# variator_380V.net
KiCad netlist of a schematic drawn in EAGLE
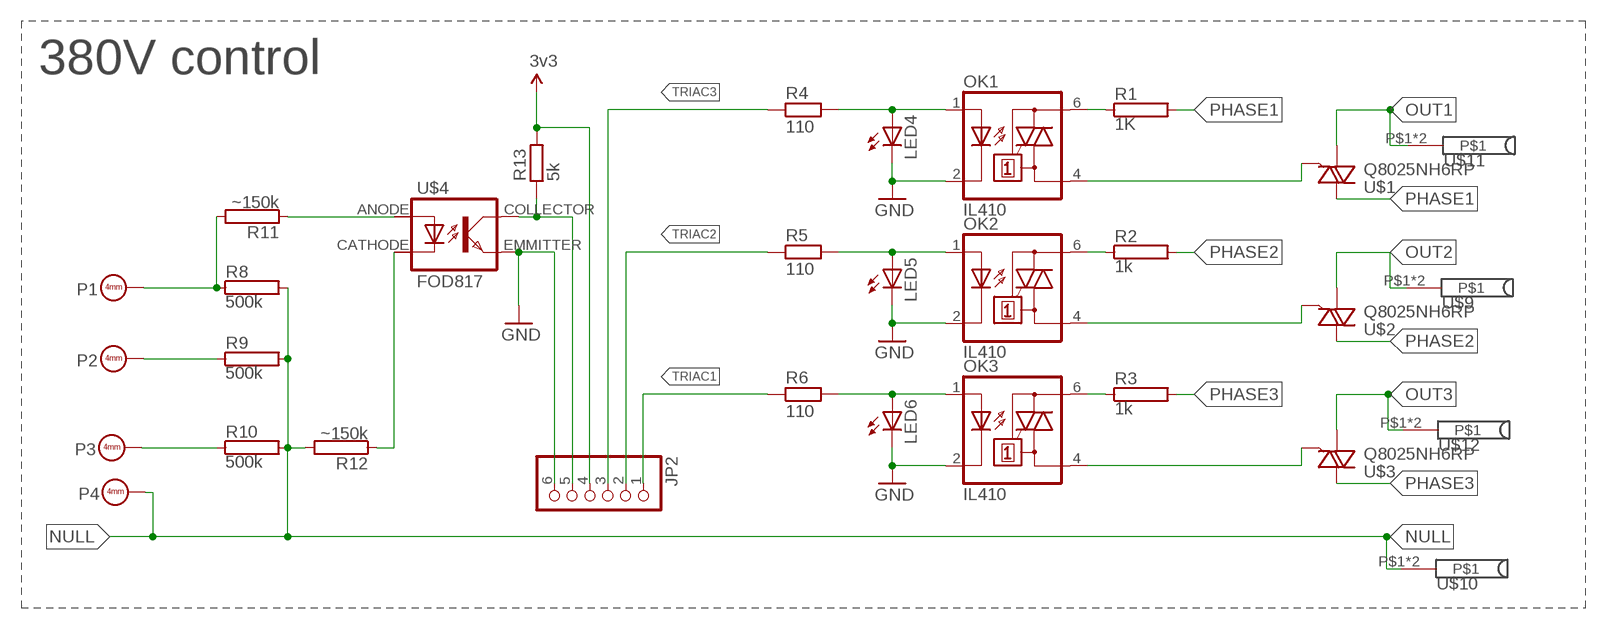
[diagram p0: schematic, sheet 1]

(export (version "E")
  (design (tool "Eeschema 10.0.6"))
  (components
    (comp (ref "JP2")
      (value "PINHD-1X6/90")
      (footprint "eagle-import:1X06_90")
      (libsource (lib "eagle-import") (part "PINHD-1X6/90"))
    )
    (comp (ref "LED4")
      (value "LED5MM")
      (footprint "eagle-import:LED5MM")
      (libsource (lib "eagle-import") (part "LED5MM"))
    )
    (comp (ref "LED5")
      (value "LED5MM")
      (footprint "eagle-import:LED5MM")
      (libsource (lib "eagle-import") (part "LED5MM"))
    )
    (comp (ref "LED6")
      (value "LED5MM")
      (footprint "eagle-import:LED5MM")
      (libsource (lib "eagle-import") (part "LED5MM"))
    )
    (comp (ref "OK1")
      (value "IL410")
      (footprint "eagle-import:DIL06")
      (fields (field (name "MF") "VISHAY/TELEFUNKEN"))
      (libsource (lib "eagle-import") (part "IL410"))
    )
    (comp (ref "OK2")
      (value "IL410")
      (footprint "eagle-import:DIL06")
      (fields (field (name "MF") "VISHAY/TELEFUNKEN"))
      (libsource (lib "eagle-import") (part "IL410"))
    )
    (comp (ref "OK3")
      (value "IL410")
      (footprint "eagle-import:DIL06")
      (fields (field (name "MF") "VISHAY/TELEFUNKEN"))
      (libsource (lib "eagle-import") (part "IL410"))
    )
    (comp (ref "P1")
      (value "BANANA")
      (footprint "eagle-import:BANANA")
      (libsource (lib "eagle-import") (part "adi_v1.4_BANANA"))
    )
    (comp (ref "P2")
      (value "BANANA")
      (footprint "eagle-import:BANANA")
      (libsource (lib "eagle-import") (part "adi_v1.4_BANANA"))
    )
    (comp (ref "P3")
      (value "BANANA")
      (footprint "eagle-import:BANANA")
      (libsource (lib "eagle-import") (part "adi_v1.4_BANANA"))
    )
    (comp (ref "P4")
      (value "BANANA")
      (footprint "eagle-import:BANANA")
      (libsource (lib "eagle-import") (part "adi_v1.4_BANANA"))
    )
    (comp (ref "R1")
      (value "1K")
      (footprint "eagle-import:HPS58")
      (libsource (lib "eagle-import") (part "RHPS58"))
    )
    (comp (ref "R2")
      (value "1k")
      (footprint "eagle-import:HPS58")
      (libsource (lib "eagle-import") (part "RHPS58"))
    )
    (comp (ref "R3")
      (value "1k")
      (footprint "eagle-import:HPS58")
      (libsource (lib "eagle-import") (part "RHPS58"))
    )
    (comp (ref "R4")
      (value "110")
      (footprint "eagle-import:1206")
      (libsource (lib "eagle-import") (part "R1206"))
    )
    (comp (ref "R5")
      (value "110")
      (footprint "eagle-import:1206")
      (libsource (lib "eagle-import") (part "R1206"))
    )
    (comp (ref "R6")
      (value "110")
      (footprint "eagle-import:1206")
      (libsource (lib "eagle-import") (part "R1206"))
    )
    (comp (ref "R8")
      (value "500k")
      (footprint "eagle-import:AC01")
      (libsource (lib "eagle-import") (part "RAC01"))
    )
    (comp (ref "R9")
      (value "500k")
      (footprint "eagle-import:AC01")
      (libsource (lib "eagle-import") (part "RAC01"))
    )
    (comp (ref "R10")
      (value "500k")
      (footprint "eagle-import:AC01")
      (libsource (lib "eagle-import") (part "RAC01"))
    )
    (comp (ref "R11")
      (value "~150k")
      (footprint "eagle-import:HPS58")
      (libsource (lib "eagle-import") (part "RHPS58"))
    )
    (comp (ref "R12")
      (value "~150k")
      (footprint "eagle-import:HPS58")
      (libsource (lib "eagle-import") (part "RHPS58"))
    )
    (comp (ref "R13")
      (value "5k")
      (footprint "eagle-import:1206")
      (libsource (lib "eagle-import") (part "R1206"))
    )
    (comp (ref "U$1")
      (value "Q8025NH6RP")
      (footprint "eagle-import:TO-263")
      (libsource (lib "eagle-import") (part "Q8025NH6RP"))
    )
    (comp (ref "U$2")
      (value "Q8025NH6RP")
      (footprint "eagle-import:TO-263")
      (libsource (lib "eagle-import") (part "Q8025NH6RP"))
    )
    (comp (ref "U$3")
      (value "Q8025NH6RP")
      (footprint "eagle-import:TO-263")
      (libsource (lib "eagle-import") (part "Q8025NH6RP"))
    )
    (comp (ref "U$4")
      (value "FOD817")
      (footprint "eagle-import:FOD_4PIN")
      (libsource (lib "eagle-import") (part "FOD817"))
    )
    (comp (ref "U$9")
      (value "BANANA")
      (footprint "eagle-import:BANANA")
      (libsource (lib "eagle-import") (part "BANANA"))
    )
    (comp (ref "U$10")
      (value "BANANA")
      (footprint "eagle-import:BANANA")
      (libsource (lib "eagle-import") (part "BANANA"))
    )
    (comp (ref "U$11")
      (value "BANANA")
      (footprint "eagle-import:BANANA")
      (libsource (lib "eagle-import") (part "BANANA"))
    )
    (comp (ref "U$12")
      (value "BANANA")
      (footprint "eagle-import:BANANA")
      (libsource (lib "eagle-import") (part "BANANA"))
    )
  )
  (nets
    (net (code "1") (name "3v3") (class "Default")
      (node (ref "JP2") (pin "4") (pinfunction "4_4") (pintype "passive"))
      (node (ref "R13") (pin "2") (pinfunction "2_2") (pintype "passive"))
    )
    (net (code "2") (name "GND") (class "Default")
      (node (ref "JP2") (pin "6") (pinfunction "6_6") (pintype "passive"))
      (node (ref "LED4") (pin "K") (pinfunction "C_K") (pintype "passive"))
      (node (ref "LED5") (pin "K") (pinfunction "C_K") (pintype "passive"))
      (node (ref "LED6") (pin "K") (pinfunction "C_K") (pintype "passive"))
      (node (ref "OK1") (pin "2") (pinfunction "C_2") (pintype "passive"))
      (node (ref "OK2") (pin "2") (pinfunction "C_2") (pintype "passive"))
      (node (ref "OK3") (pin "2") (pinfunction "C_2") (pintype "passive"))
      (node (ref "U$4") (pin "EMMITTER") (pinfunction "EMIT_EMMITTER") (pintype "passive"))
    )
    (net (code "3") (name "NULL") (class "Default")
      (node (ref "P4") (pin "P$1") (pinfunction "1_P$1") (pintype "passive"))
      (node (ref "R10") (pin "2") (pinfunction "2_2") (pintype "passive"))
      (node (ref "R12") (pin "2") (pinfunction "2_2") (pintype "passive"))
      (node (ref "R8") (pin "2") (pinfunction "2_2") (pintype "passive"))
      (node (ref "R9") (pin "2") (pinfunction "2_2") (pintype "passive"))
      (node (ref "U$10") (pin "P$1") (pinfunction "P$1_P$1") (pintype "bidirectional"))
      (node (ref "U$10") (pin "P$2") (pinfunction "P$1_P$2") (pintype "bidirectional"))
    )
    (net (code "4") (name "Net-(OK1-A)") (class "Default")
      (node (ref "LED4") (pin "A") (pinfunction "A_A") (pintype "passive"))
      (node (ref "OK1") (pin "1") (pinfunction "A_1") (pintype "passive"))
      (node (ref "R4") (pin "2") (pinfunction "2_2") (pintype "passive"))
    )
    (net (code "5") (name "Net-(OK1-A1)") (class "Default")
      (node (ref "OK1") (pin "4") (pinfunction "A1_4") (pintype "passive"))
      (node (ref "U$1") (pin "G") (pinfunction "G_G") (pintype "passive"))
    )
    (net (code "6") (name "Net-(OK1-A2)") (class "Default")
      (node (ref "OK1") (pin "6") (pinfunction "A2_6") (pintype "passive"))
      (node (ref "R1") (pin "1") (pinfunction "1_1") (pintype "passive"))
    )
    (net (code "7") (name "Net-(OK2-A)") (class "Default")
      (node (ref "LED5") (pin "A") (pinfunction "A_A") (pintype "passive"))
      (node (ref "OK2") (pin "1") (pinfunction "A_1") (pintype "passive"))
      (node (ref "R5") (pin "2") (pinfunction "2_2") (pintype "passive"))
    )
    (net (code "8") (name "Net-(OK2-A1)") (class "Default")
      (node (ref "OK2") (pin "4") (pinfunction "A1_4") (pintype "passive"))
      (node (ref "U$2") (pin "G") (pinfunction "G_G") (pintype "passive"))
    )
    (net (code "9") (name "Net-(OK2-A2)") (class "Default")
      (node (ref "OK2") (pin "6") (pinfunction "A2_6") (pintype "passive"))
      (node (ref "R2") (pin "1") (pinfunction "1_1") (pintype "passive"))
    )
    (net (code "10") (name "Net-(OK3-A)") (class "Default")
      (node (ref "LED6") (pin "A") (pinfunction "A_A") (pintype "passive"))
      (node (ref "OK3") (pin "1") (pinfunction "A_1") (pintype "passive"))
      (node (ref "R6") (pin "2") (pinfunction "2_2") (pintype "passive"))
    )
    (net (code "11") (name "Net-(OK3-A1)") (class "Default")
      (node (ref "OK3") (pin "4") (pinfunction "A1_4") (pintype "passive"))
      (node (ref "U$3") (pin "G") (pinfunction "G_G") (pintype "passive"))
    )
    (net (code "12") (name "Net-(OK3-A2)") (class "Default")
      (node (ref "OK3") (pin "6") (pinfunction "A2_6") (pintype "passive"))
      (node (ref "R3") (pin "1") (pinfunction "1_1") (pintype "passive"))
    )
    (net (code "13") (name "Net-(R11-Pad1)") (class "Default")
      (node (ref "R11") (pin "1") (pinfunction "1_1") (pintype "passive"))
      (node (ref "U$4") (pin "ANODE") (pinfunction "ANODE_ANODE") (pintype "passive"))
    )
    (net (code "14") (name "Net-(R12-Pad1)") (class "Default")
      (node (ref "R12") (pin "1") (pinfunction "1_1") (pintype "passive"))
      (node (ref "U$4") (pin "CATHODE") (pinfunction "CATHODE_CATHODE") (pintype "passive"))
    )
    (net (code "15") (name "Net-(U$4-COL)") (class "Default")
      (node (ref "JP2") (pin "5") (pinfunction "5_5") (pintype "passive"))
      (node (ref "R13") (pin "1") (pinfunction "1_1") (pintype "passive"))
      (node (ref "U$4") (pin "COLLECTOR") (pinfunction "COL_COLLECTOR") (pintype "passive"))
    )
    (net (code "16") (name "OUT1") (class "Default")
      (node (ref "U$1") (pin "T1") (pinfunction "T1_T1") (pintype "passive"))
      (node (ref "U$11") (pin "P$1") (pinfunction "P$1_P$1") (pintype "bidirectional"))
      (node (ref "U$11") (pin "P$2") (pinfunction "P$1_P$2") (pintype "bidirectional"))
    )
    (net (code "17") (name "OUT2") (class "Default")
      (node (ref "U$2") (pin "T1") (pinfunction "T1_T1") (pintype "passive"))
      (node (ref "U$9") (pin "P$1") (pinfunction "P$1_P$1") (pintype "bidirectional"))
      (node (ref "U$9") (pin "P$2") (pinfunction "P$1_P$2") (pintype "bidirectional"))
    )
    (net (code "18") (name "OUT3") (class "Default")
      (node (ref "U$12") (pin "P$1") (pinfunction "P$1_P$1") (pintype "bidirectional"))
      (node (ref "U$12") (pin "P$2") (pinfunction "P$1_P$2") (pintype "bidirectional"))
      (node (ref "U$3") (pin "T1") (pinfunction "T1_T1") (pintype "passive"))
    )
    (net (code "19") (name "PHASE1") (class "Default")
      (node (ref "P1") (pin "P$1") (pinfunction "1_P$1") (pintype "passive"))
      (node (ref "R1") (pin "2") (pinfunction "2_2") (pintype "passive"))
      (node (ref "R11") (pin "2") (pinfunction "2_2") (pintype "passive"))
      (node (ref "R8") (pin "1") (pinfunction "1_1") (pintype "passive"))
      (node (ref "U$1") (pin "T2") (pinfunction "T2_T2") (pintype "passive"))
    )
    (net (code "20") (name "PHASE2") (class "Default")
      (node (ref "P2") (pin "P$1") (pinfunction "1_P$1") (pintype "passive"))
      (node (ref "R2") (pin "2") (pinfunction "2_2") (pintype "passive"))
      (node (ref "R9") (pin "1") (pinfunction "1_1") (pintype "passive"))
      (node (ref "U$2") (pin "T2") (pinfunction "T2_T2") (pintype "passive"))
    )
    (net (code "21") (name "PHASE3") (class "Default")
      (node (ref "P3") (pin "P$1") (pinfunction "1_P$1") (pintype "passive"))
      (node (ref "R10") (pin "1") (pinfunction "1_1") (pintype "passive"))
      (node (ref "R3") (pin "2") (pinfunction "2_2") (pintype "passive"))
      (node (ref "U$3") (pin "T2") (pinfunction "T2_T2") (pintype "passive"))
    )
    (net (code "22") (name "TRIAC1") (class "Default")
      (node (ref "JP2") (pin "1") (pinfunction "1_1") (pintype "passive"))
      (node (ref "R6") (pin "1") (pinfunction "1_1") (pintype "passive"))
    )
    (net (code "23") (name "TRIAC2") (class "Default")
      (node (ref "JP2") (pin "2") (pinfunction "2_2") (pintype "passive"))
      (node (ref "R5") (pin "1") (pinfunction "1_1") (pintype "passive"))
    )
    (net (code "24") (name "TRIAC3") (class "Default")
      (node (ref "JP2") (pin "3") (pinfunction "3_3") (pintype "passive"))
      (node (ref "R4") (pin "1") (pinfunction "1_1") (pintype "passive"))
    )
  )
)
